# encoder.net
KiCad netlist of a schematic drawn in EAGLE
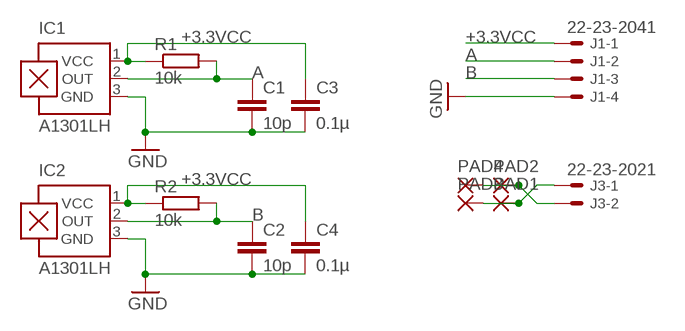
[diagram p0: schematic, sheet 1]

(export (version "E")
  (design (tool "Eeschema 10.0.6"))
  (components
    (comp (ref "C1")
      (value "10p")
      (footprint "eagle-import:C0805")
      (libsource (lib "eagle-import") (part "C-EUC0805"))
    )
    (comp (ref "C2")
      (value "10p")
      (footprint "eagle-import:C0805")
      (libsource (lib "eagle-import") (part "C-EUC0805"))
    )
    (comp (ref "C3")
      (value "0.1µ")
      (footprint "eagle-import:C0805")
      (libsource (lib "eagle-import") (part "C-EUC0805"))
    )
    (comp (ref "C4")
      (value "0.1µ")
      (footprint "eagle-import:C0805")
      (libsource (lib "eagle-import") (part "C-EUC0805"))
    )
    (comp (ref "IC1")
      (value "A1301LH")
      (footprint "eagle-import:SOT23-W")
      (fields (field (name "MF") "ALLEGRO MICROSYSTEMS, INC.") (field (name "MPN") "A1301ELHLT-T"))
      (libsource (lib "eagle-import") (part "A13?LH01"))
    )
    (comp (ref "IC2")
      (value "A1301LH")
      (footprint "eagle-import:SOT23-W")
      (fields (field (name "MF") "ALLEGRO MICROSYSTEMS, INC.") (field (name "MPN") "A1301ELHLT-T"))
      (libsource (lib "eagle-import") (part "A13?LH01"))
    )
    (comp (ref "J1")
      (value "22-23-2041")
      (footprint "eagle-import:22-23-2041")
      (fields (field (name "MF") "MOLEX"))
      (libsource (lib "eagle-import") (part "22-23-2041"))
    )
    (comp (ref "J3")
      (value "22-23-2021")
      (footprint "eagle-import:22-23-2021")
      (fields (field (name "MF") "MOLEX"))
      (libsource (lib "eagle-import") (part "22-23-2021"))
    )
    (comp (ref "PAD1")
      (value "3,81/1,4")
      (footprint "eagle-import:3,81_1,4")
      (libsource (lib "eagle-import") (part "3,81/1,4"))
    )
    (comp (ref "PAD2")
      (value "3,81/1,4")
      (footprint "eagle-import:3,81_1,4")
      (libsource (lib "eagle-import") (part "3,81/1,4"))
    )
    (comp (ref "PAD3")
      (value "3,81/1,4")
      (footprint "eagle-import:3,81_1,4")
      (libsource (lib "eagle-import") (part "3,81/1,4"))
    )
    (comp (ref "PAD4")
      (value "3,81/1,4")
      (footprint "eagle-import:3,81_1,4")
      (libsource (lib "eagle-import") (part "3,81/1,4"))
    )
    (comp (ref "R1")
      (value "10k")
      (footprint "eagle-import:R0805")
      (libsource (lib "eagle-import") (part "R-EU_R0805"))
    )
    (comp (ref "R2")
      (value "10k")
      (footprint "eagle-import:R0805")
      (libsource (lib "eagle-import") (part "R-EU_R0805"))
    )
  )
  (nets
    (net (code "1") (name "/+3.3VCC") (class "Default")
      (node (ref "C3") (pin "1") (pinfunction "1_1") (pintype "passive"))
      (node (ref "C4") (pin "1") (pinfunction "1_1") (pintype "passive"))
      (node (ref "IC1") (pin "1") (pinfunction "VCC_1") (pintype "power_in"))
      (node (ref "IC2") (pin "1") (pinfunction "VCC_1") (pintype "power_in"))
      (node (ref "J1") (pin "1") (pinfunction "S_1") (pintype "passive"))
      (node (ref "R1") (pin "1") (pinfunction "1_1") (pintype "passive"))
      (node (ref "R2") (pin "1") (pinfunction "1_1") (pintype "passive"))
    )
    (net (code "2") (name "/A") (class "Default")
      (node (ref "C1") (pin "1") (pinfunction "1_1") (pintype "passive"))
      (node (ref "IC1") (pin "2") (pinfunction "OUT_2") (pintype "output"))
      (node (ref "J1") (pin "2") (pinfunction "S_2") (pintype "passive"))
      (node (ref "R1") (pin "2") (pinfunction "2_2") (pintype "passive"))
    )
    (net (code "3") (name "/B") (class "Default")
      (node (ref "C2") (pin "1") (pinfunction "1_1") (pintype "passive"))
      (node (ref "IC2") (pin "2") (pinfunction "OUT_2") (pintype "output"))
      (node (ref "J1") (pin "3") (pinfunction "S_3") (pintype "passive"))
      (node (ref "R2") (pin "2") (pinfunction "2_2") (pintype "passive"))
    )
    (net (code "4") (name "GND") (class "Default")
      (node (ref "C1") (pin "2") (pinfunction "2_2") (pintype "passive"))
      (node (ref "C2") (pin "2") (pinfunction "2_2") (pintype "passive"))
      (node (ref "C3") (pin "2") (pinfunction "2_2") (pintype "passive"))
      (node (ref "C4") (pin "2") (pinfunction "2_2") (pintype "passive"))
      (node (ref "IC1") (pin "3") (pinfunction "GND_3") (pintype "power_in"))
      (node (ref "IC2") (pin "3") (pinfunction "GND_3") (pintype "power_in"))
      (node (ref "J1") (pin "4") (pinfunction "S_4") (pintype "passive"))
    )
    (net (code "5") (name "Net-(J3A-S)") (class "Default")
      (node (ref "J3") (pin "1") (pinfunction "S_1") (pintype "passive"))
      (node (ref "PAD1") (pin "1") (pinfunction "P_1") (pintype "passive"))
      (node (ref "PAD3") (pin "1") (pinfunction "P_1") (pintype "passive"))
    )
    (net (code "6") (name "Net-(J3B-S)") (class "Default")
      (node (ref "J3") (pin "2") (pinfunction "S_2") (pintype "passive"))
      (node (ref "PAD2") (pin "1") (pinfunction "P_1") (pintype "passive"))
      (node (ref "PAD4") (pin "1") (pinfunction "P_1") (pintype "passive"))
    )
  )
)
